# slave-16-mosfet.net
KiCad netlist of a schematic drawn in EAGLE
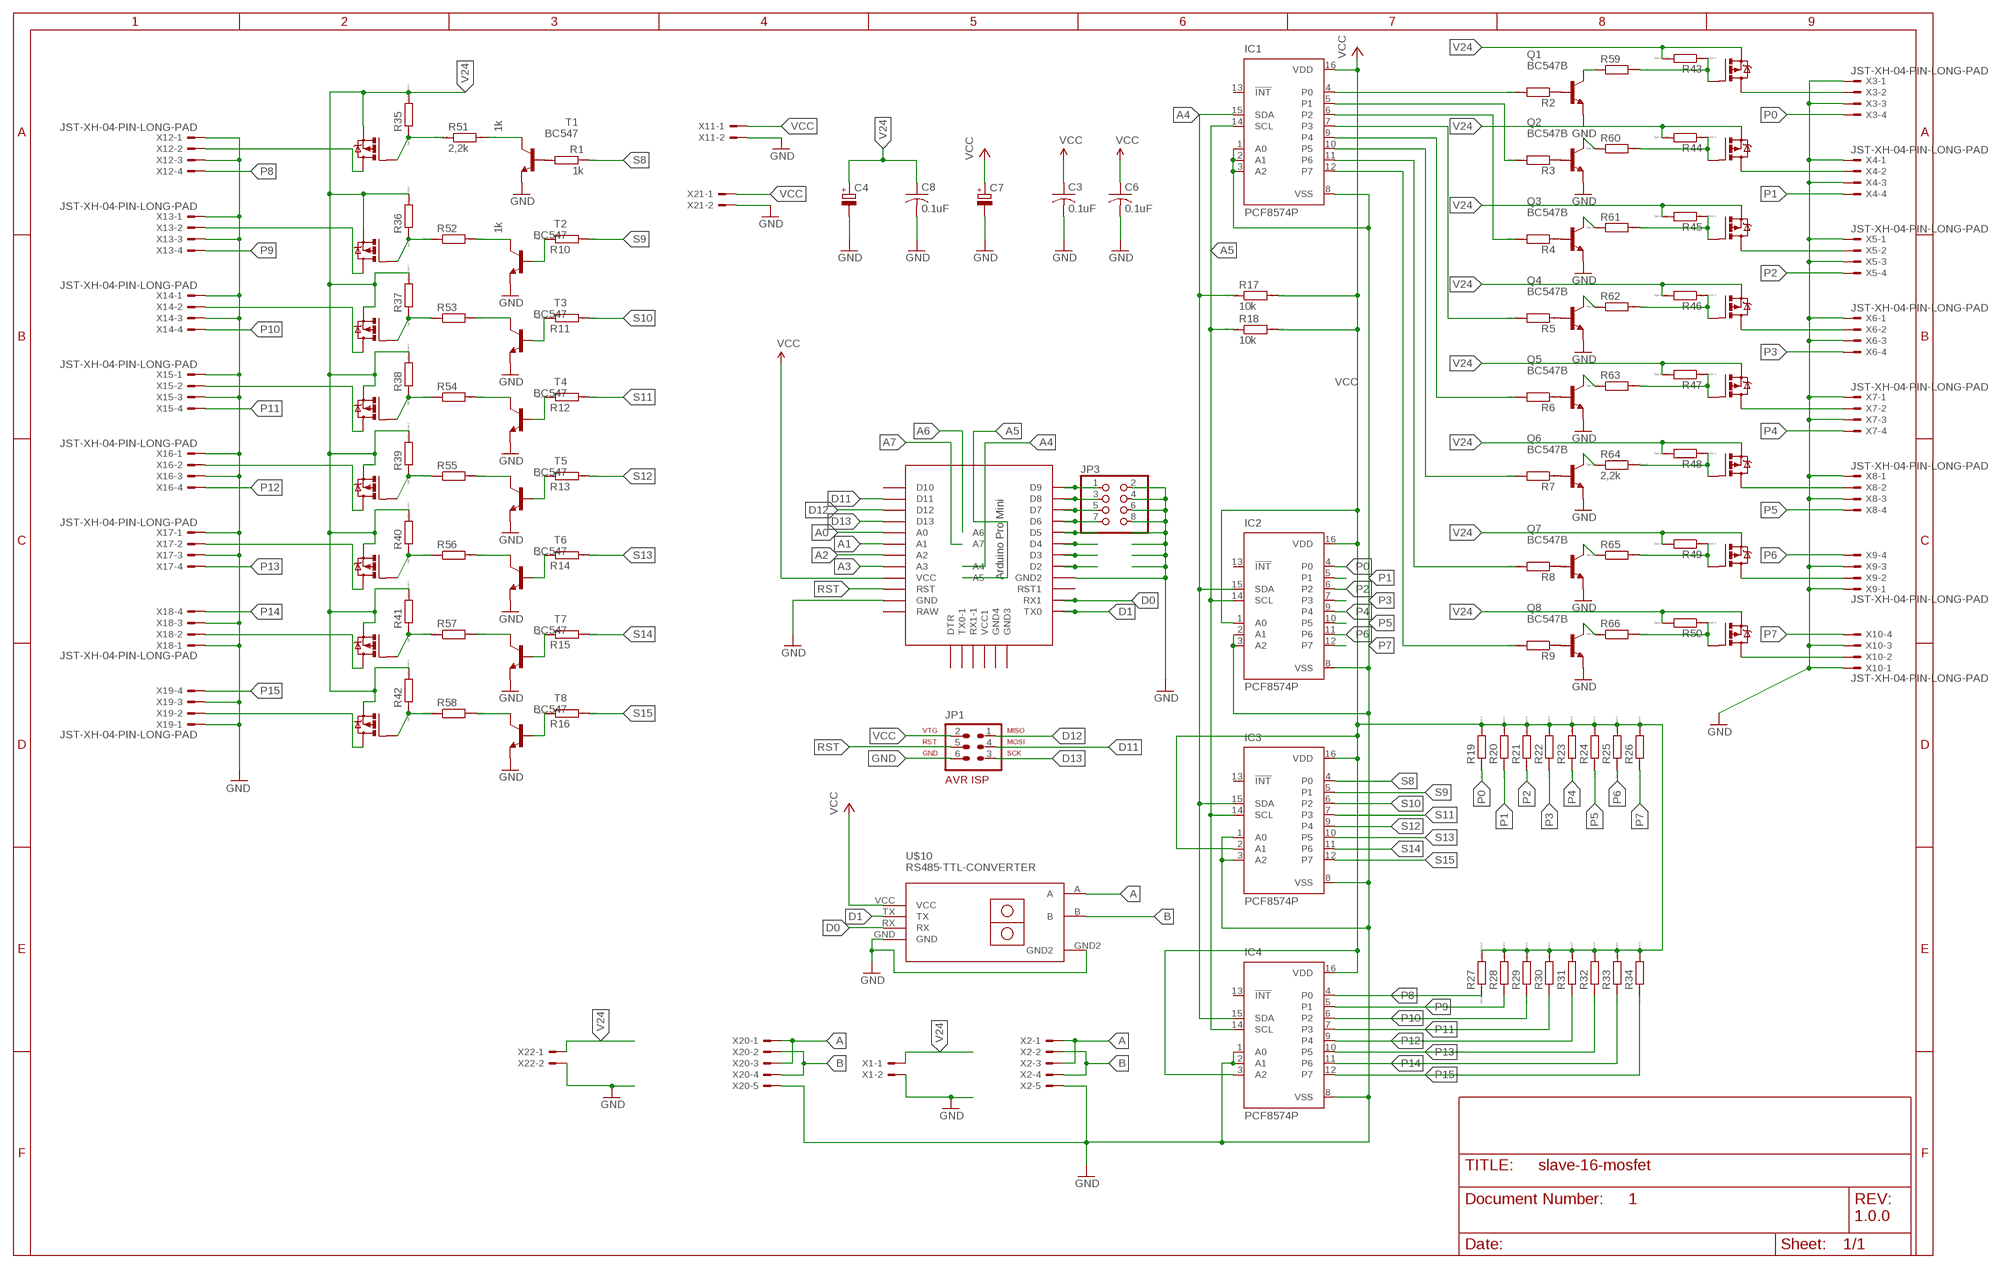
[diagram p0: schematic, sheet 1]

(export (version "E")
  (design (tool "Eeschema 10.0.6"))
  (components
    (comp (ref "C3")
      (value "0.1uF")
      (footprint "eagle-import:C0805")
      (libsource (lib "eagle-import") (part "C-USC0805"))
    )
    (comp (ref "C4")
      (value "CPOL-EUSANYO_SMD_C6")
      (footprint "eagle-import:SANYO-OSCON_SMD_C6")
      (libsource (lib "eagle-import") (part "CPOL-EUSANYO_SMD_C6"))
    )
    (comp (ref "C6")
      (value "0.1uF")
      (footprint "eagle-import:C0805")
      (libsource (lib "eagle-import") (part "C-USC0805"))
    )
    (comp (ref "C7")
      (value "CPOL-EUSANYO_SMD_C6")
      (footprint "eagle-import:SANYO-OSCON_SMD_C6")
      (libsource (lib "eagle-import") (part "CPOL-EUSANYO_SMD_C6"))
    )
    (comp (ref "C8")
      (value "0.1uF")
      (footprint "eagle-import:C0805")
      (libsource (lib "eagle-import") (part "C-USC0805"))
    )
    (comp (ref "IC1")
      (value "PCF8574P")
      (footprint "eagle-import:DIL16")
      (fields (field (name "MPN") "PCF8574PN"))
      (libsource (lib "eagle-import") (part "PCF8574P"))
    )
    (comp (ref "IC2")
      (value "PCF8574P")
      (footprint "eagle-import:DIL16")
      (fields (field (name "MPN") "PCF8574PN"))
      (libsource (lib "eagle-import") (part "PCF8574P"))
    )
    (comp (ref "IC3")
      (value "PCF8574P")
      (footprint "eagle-import:DIL16")
      (fields (field (name "MPN") "PCF8574PN"))
      (libsource (lib "eagle-import") (part "PCF8574P"))
    )
    (comp (ref "IC4")
      (value "PCF8574P")
      (footprint "eagle-import:DIL16")
      (fields (field (name "MPN") "PCF8574PN"))
      (libsource (lib "eagle-import") (part "PCF8574P"))
    )
    (comp (ref "JP1")
      (value "AVR-ISP-6")
      (footprint "eagle-import:AVR-ISP-6")
      (libsource (lib "eagle-import") (part "AVR-ISP-6"))
    )
    (comp (ref "JP3")
      (value "PINHD-2X4")
      (footprint "eagle-import:2X04")
      (libsource (lib "eagle-import") (part "PINHD-2X4"))
    )
    (comp (ref "Q1")
      (value "BC547B")
      (footprint "eagle-import:TO92")
      (libsource (lib "eagle-import") (part "BC547B"))
    )
    (comp (ref "Q2")
      (value "BC547B")
      (footprint "eagle-import:TO92")
      (libsource (lib "eagle-import") (part "BC547B"))
    )
    (comp (ref "Q3")
      (value "BC547B")
      (footprint "eagle-import:TO92")
      (libsource (lib "eagle-import") (part "BC547B"))
    )
    (comp (ref "Q4")
      (value "BC547B")
      (footprint "eagle-import:TO92")
      (libsource (lib "eagle-import") (part "BC547B"))
    )
    (comp (ref "Q5")
      (value "BC547B")
      (footprint "eagle-import:TO92")
      (libsource (lib "eagle-import") (part "BC547B"))
    )
    (comp (ref "Q6")
      (value "BC547B")
      (footprint "eagle-import:TO92")
      (libsource (lib "eagle-import") (part "BC547B"))
    )
    (comp (ref "Q7")
      (value "BC547B")
      (footprint "eagle-import:TO92")
      (libsource (lib "eagle-import") (part "BC547B"))
    )
    (comp (ref "Q8")
      (value "BC547B")
      (footprint "eagle-import:TO92")
      (libsource (lib "eagle-import") (part "BC547B"))
    )
    (comp (ref "R1")
      (value "1k")
      (footprint "eagle-import:R1206")
      (libsource (lib "eagle-import") (part "RR1206"))
    )
    (comp (ref "R2")
      (value "RR1206")
      (footprint "eagle-import:R1206")
      (libsource (lib "eagle-import") (part "RR1206"))
    )
    (comp (ref "R3")
      (value "RR1206")
      (footprint "eagle-import:R1206")
      (libsource (lib "eagle-import") (part "RR1206"))
    )
    (comp (ref "R4")
      (value "RR1206")
      (footprint "eagle-import:R1206")
      (libsource (lib "eagle-import") (part "RR1206"))
    )
    (comp (ref "R5")
      (value "RR1206")
      (footprint "eagle-import:R1206")
      (libsource (lib "eagle-import") (part "RR1206"))
    )
    (comp (ref "R6")
      (value "RR1206")
      (footprint "eagle-import:R1206")
      (libsource (lib "eagle-import") (part "RR1206"))
    )
    (comp (ref "R7")
      (value "RR1206")
      (footprint "eagle-import:R1206")
      (libsource (lib "eagle-import") (part "RR1206"))
    )
    (comp (ref "R8")
      (value "RR1206")
      (footprint "eagle-import:R1206")
      (libsource (lib "eagle-import") (part "RR1206"))
    )
    (comp (ref "R9")
      (value "RR1206")
      (footprint "eagle-import:R1206")
      (libsource (lib "eagle-import") (part "RR1206"))
    )
    (comp (ref "R10")
      (value "RR1206")
      (footprint "eagle-import:R1206")
      (libsource (lib "eagle-import") (part "RR1206"))
    )
    (comp (ref "R11")
      (value "RR1206")
      (footprint "eagle-import:R1206")
      (libsource (lib "eagle-import") (part "RR1206"))
    )
    (comp (ref "R12")
      (value "RR1206")
      (footprint "eagle-import:R1206")
      (libsource (lib "eagle-import") (part "RR1206"))
    )
    (comp (ref "R13")
      (value "RR1206")
      (footprint "eagle-import:R1206")
      (libsource (lib "eagle-import") (part "RR1206"))
    )
    (comp (ref "R14")
      (value "RR1206")
      (footprint "eagle-import:R1206")
      (libsource (lib "eagle-import") (part "RR1206"))
    )
    (comp (ref "R15")
      (value "RR1206")
      (footprint "eagle-import:R1206")
      (libsource (lib "eagle-import") (part "RR1206"))
    )
    (comp (ref "R16")
      (value "RR1206")
      (footprint "eagle-import:R1206")
      (libsource (lib "eagle-import") (part "RR1206"))
    )
    (comp (ref "R17")
      (value "10k")
      (footprint "eagle-import:R1206")
      (libsource (lib "eagle-import") (part "RR1206"))
    )
    (comp (ref "R18")
      (value "10k")
      (footprint "eagle-import:R1206")
      (libsource (lib "eagle-import") (part "RR1206"))
    )
    (comp (ref "R19")
      (value "RR1206")
      (footprint "eagle-import:R1206")
      (libsource (lib "eagle-import") (part "RR1206"))
    )
    (comp (ref "R20")
      (value "RR1206")
      (footprint "eagle-import:R1206")
      (libsource (lib "eagle-import") (part "RR1206"))
    )
    (comp (ref "R21")
      (value "RR1206")
      (footprint "eagle-import:R1206")
      (libsource (lib "eagle-import") (part "RR1206"))
    )
    (comp (ref "R22")
      (value "RR1206")
      (footprint "eagle-import:R1206")
      (libsource (lib "eagle-import") (part "RR1206"))
    )
    (comp (ref "R23")
      (value "RR1206")
      (footprint "eagle-import:R1206")
      (libsource (lib "eagle-import") (part "RR1206"))
    )
    (comp (ref "R24")
      (value "RR1206")
      (footprint "eagle-import:R1206")
      (libsource (lib "eagle-import") (part "RR1206"))
    )
    (comp (ref "R25")
      (value "RR1206")
      (footprint "eagle-import:R1206")
      (libsource (lib "eagle-import") (part "RR1206"))
    )
    (comp (ref "R26")
      (value "RR1206")
      (footprint "eagle-import:R1206")
      (libsource (lib "eagle-import") (part "RR1206"))
    )
    (comp (ref "R27")
      (value "RR1206")
      (footprint "eagle-import:R1206")
      (libsource (lib "eagle-import") (part "RR1206"))
    )
    (comp (ref "R28")
      (value "RR1206")
      (footprint "eagle-import:R1206")
      (libsource (lib "eagle-import") (part "RR1206"))
    )
    (comp (ref "R29")
      (value "RR1206")
      (footprint "eagle-import:R1206")
      (libsource (lib "eagle-import") (part "RR1206"))
    )
    (comp (ref "R30")
      (value "RR1206")
      (footprint "eagle-import:R1206")
      (libsource (lib "eagle-import") (part "RR1206"))
    )
    (comp (ref "R31")
      (value "RR1206")
      (footprint "eagle-import:R1206")
      (libsource (lib "eagle-import") (part "RR1206"))
    )
    (comp (ref "R32")
      (value "RR1206")
      (footprint "eagle-import:R1206")
      (libsource (lib "eagle-import") (part "RR1206"))
    )
    (comp (ref "R33")
      (value "RR1206")
      (footprint "eagle-import:R1206")
      (libsource (lib "eagle-import") (part "RR1206"))
    )
    (comp (ref "R34")
      (value "RR1206")
      (footprint "eagle-import:R1206")
      (libsource (lib "eagle-import") (part "RR1206"))
    )
    (comp (ref "R35")
      (value "1k")
      (footprint "eagle-import:R1206")
      (libsource (lib "eagle-import") (part "RR1206"))
    )
    (comp (ref "R36")
      (value "1k")
      (footprint "eagle-import:R1206")
      (libsource (lib "eagle-import") (part "RR1206"))
    )
    (comp (ref "R37")
      (value "RR1206")
      (footprint "eagle-import:R1206")
      (libsource (lib "eagle-import") (part "RR1206"))
    )
    (comp (ref "R38")
      (value "RR1206")
      (footprint "eagle-import:R1206")
      (libsource (lib "eagle-import") (part "RR1206"))
    )
    (comp (ref "R39")
      (value "RR1206")
      (footprint "eagle-import:R1206")
      (libsource (lib "eagle-import") (part "RR1206"))
    )
    (comp (ref "R40")
      (value "RR1206")
      (footprint "eagle-import:R1206")
      (libsource (lib "eagle-import") (part "RR1206"))
    )
    (comp (ref "R41")
      (value "RR1206")
      (footprint "eagle-import:R1206")
      (libsource (lib "eagle-import") (part "RR1206"))
    )
    (comp (ref "R42")
      (value "RR1206")
      (footprint "eagle-import:R1206")
      (libsource (lib "eagle-import") (part "RR1206"))
    )
    (comp (ref "R43")
      (value "RR1206")
      (footprint "eagle-import:R1206")
      (libsource (lib "eagle-import") (part "RR1206"))
    )
    (comp (ref "R44")
      (value "RR1206")
      (footprint "eagle-import:R1206")
      (libsource (lib "eagle-import") (part "RR1206"))
    )
    (comp (ref "R45")
      (value "RR1206")
      (footprint "eagle-import:R1206")
      (libsource (lib "eagle-import") (part "RR1206"))
    )
    (comp (ref "R46")
      (value "RR1206")
      (footprint "eagle-import:R1206")
      (libsource (lib "eagle-import") (part "RR1206"))
    )
    (comp (ref "R47")
      (value "RR1206")
      (footprint "eagle-import:R1206")
      (libsource (lib "eagle-import") (part "RR1206"))
    )
    (comp (ref "R48")
      (value "RR1206")
      (footprint "eagle-import:R1206")
      (libsource (lib "eagle-import") (part "RR1206"))
    )
    (comp (ref "R49")
      (value "RR1206")
      (footprint "eagle-import:R1206")
      (libsource (lib "eagle-import") (part "RR1206"))
    )
    (comp (ref "R50")
      (value "RR1206")
      (footprint "eagle-import:R1206")
      (libsource (lib "eagle-import") (part "RR1206"))
    )
    (comp (ref "R51")
      (value "2,2k")
      (footprint "eagle-import:R1206")
      (libsource (lib "eagle-import") (part "RR1206"))
    )
    (comp (ref "R52")
      (value "RR1206")
      (footprint "eagle-import:R1206")
      (libsource (lib "eagle-import") (part "RR1206"))
    )
    (comp (ref "R53")
      (value "RR1206")
      (footprint "eagle-import:R1206")
      (libsource (lib "eagle-import") (part "RR1206"))
    )
    (comp (ref "R54")
      (value "RR1206")
      (footprint "eagle-import:R1206")
      (libsource (lib "eagle-import") (part "RR1206"))
    )
    (comp (ref "R55")
      (value "RR1206")
      (footprint "eagle-import:R1206")
      (libsource (lib "eagle-import") (part "RR1206"))
    )
    (comp (ref "R56")
      (value "RR1206")
      (footprint "eagle-import:R1206")
      (libsource (lib "eagle-import") (part "RR1206"))
    )
    (comp (ref "R57")
      (value "RR1206")
      (footprint "eagle-import:R1206")
      (libsource (lib "eagle-import") (part "RR1206"))
    )
    (comp (ref "R58")
      (value "RR1206")
      (footprint "eagle-import:R1206")
      (libsource (lib "eagle-import") (part "RR1206"))
    )
    (comp (ref "R59")
      (value "RR1206")
      (footprint "eagle-import:R1206")
      (libsource (lib "eagle-import") (part "RR1206"))
    )
    (comp (ref "R60")
      (value "RR1206")
      (footprint "eagle-import:R1206")
      (libsource (lib "eagle-import") (part "RR1206"))
    )
    (comp (ref "R61")
      (value "RR1206")
      (footprint "eagle-import:R1206")
      (libsource (lib "eagle-import") (part "RR1206"))
    )
    (comp (ref "R62")
      (value "RR1206")
      (footprint "eagle-import:R1206")
      (libsource (lib "eagle-import") (part "RR1206"))
    )
    (comp (ref "R63")
      (value "RR1206")
      (footprint "eagle-import:R1206")
      (libsource (lib "eagle-import") (part "RR1206"))
    )
    (comp (ref "R64")
      (value "2,2k")
      (footprint "eagle-import:R1206")
      (libsource (lib "eagle-import") (part "RR1206"))
    )
    (comp (ref "R65")
      (value "RR1206")
      (footprint "eagle-import:R1206")
      (libsource (lib "eagle-import") (part "RR1206"))
    )
    (comp (ref "R66")
      (value "RR1206")
      (footprint "eagle-import:R1206")
      (libsource (lib "eagle-import") (part "RR1206"))
    )
    (comp (ref "T1")
      (value "BC547")
      (footprint "eagle-import:TO92")
      (libsource (lib "eagle-import") (part "transistor_402_BC547"))
    )
    (comp (ref "T2")
      (value "BC547")
      (footprint "eagle-import:TO92")
      (libsource (lib "eagle-import") (part "transistor_402_BC547"))
    )
    (comp (ref "T3")
      (value "BC547")
      (footprint "eagle-import:TO92")
      (libsource (lib "eagle-import") (part "transistor_402_BC547"))
    )
    (comp (ref "T4")
      (value "BC547")
      (footprint "eagle-import:TO92")
      (libsource (lib "eagle-import") (part "transistor_402_BC547"))
    )
    (comp (ref "T5")
      (value "BC547")
      (footprint "eagle-import:TO92")
      (libsource (lib "eagle-import") (part "transistor_402_BC547"))
    )
    (comp (ref "T6")
      (value "BC547")
      (footprint "eagle-import:TO92")
      (libsource (lib "eagle-import") (part "transistor_402_BC547"))
    )
    (comp (ref "T7")
      (value "BC547")
      (footprint "eagle-import:TO92")
      (libsource (lib "eagle-import") (part "transistor_402_BC547"))
    )
    (comp (ref "T8")
      (value "BC547")
      (footprint "eagle-import:TO92")
      (libsource (lib "eagle-import") (part "transistor_402_BC547"))
    )
    (comp (ref "U$1")
      (value "IRF9530")
      (footprint "eagle-import:TO220BV")
      (libsource (lib "eagle-import") (part "IRF9530"))
    )
    (comp (ref "U$2")
      (value "IRF9530")
      (footprint "eagle-import:TO220BV")
      (libsource (lib "eagle-import") (part "IRF9530"))
    )
    (comp (ref "U$3")
      (value "IRF9530")
      (footprint "eagle-import:TO220BV")
      (libsource (lib "eagle-import") (part "IRF9530"))
    )
    (comp (ref "U$4")
      (value "IRF9530")
      (footprint "eagle-import:TO220BV")
      (libsource (lib "eagle-import") (part "IRF9530"))
    )
    (comp (ref "U$5")
      (value "IRF9530")
      (footprint "eagle-import:TO220BV")
      (libsource (lib "eagle-import") (part "IRF9530"))
    )
    (comp (ref "U$6")
      (value "IRF9530")
      (footprint "eagle-import:TO220BV")
      (libsource (lib "eagle-import") (part "IRF9530"))
    )
    (comp (ref "U$7")
      (value "IRF9530")
      (footprint "eagle-import:TO220BV")
      (libsource (lib "eagle-import") (part "IRF9530"))
    )
    (comp (ref "U$8")
      (value "IRF9530")
      (footprint "eagle-import:TO220BV")
      (libsource (lib "eagle-import") (part "IRF9530"))
    )
    (comp (ref "U$10")
      (value "RS485-TTL-CONVERTER")
      (footprint "eagle-import:RS485-TTL-CONVERTER")
      (libsource (lib "eagle-import") (part "RS485-TTL-CONVERTER"))
    )
    (comp (ref "U$12")
      (value "IRF9530")
      (footprint "eagle-import:TO220BV")
      (libsource (lib "eagle-import") (part "IRF9530"))
    )
    (comp (ref "U$13")
      (value "IRF9530")
      (footprint "eagle-import:TO220BV")
      (libsource (lib "eagle-import") (part "IRF9530"))
    )
    (comp (ref "U$14")
      (value "IRF9530")
      (footprint "eagle-import:TO220BV")
      (libsource (lib "eagle-import") (part "IRF9530"))
    )
    (comp (ref "U$15")
      (value "IRF9530")
      (footprint "eagle-import:TO220BV")
      (libsource (lib "eagle-import") (part "IRF9530"))
    )
    (comp (ref "U$16")
      (value "IRF9530")
      (footprint "eagle-import:TO220BV")
      (libsource (lib "eagle-import") (part "IRF9530"))
    )
    (comp (ref "U$17")
      (value "IRF9530")
      (footprint "eagle-import:TO220BV")
      (libsource (lib "eagle-import") (part "IRF9530"))
    )
    (comp (ref "U$18")
      (value "IRF9530")
      (footprint "eagle-import:TO220BV")
      (libsource (lib "eagle-import") (part "IRF9530"))
    )
    (comp (ref "U$19")
      (value "IRF9530")
      (footprint "eagle-import:TO220BV")
      (libsource (lib "eagle-import") (part "IRF9530"))
    )
    (comp (ref "U$20")
      (value "PRO-MINI-2")
      (footprint "eagle-import:PRO-MINI-2")
      (libsource (lib "eagle-import") (part "PRO-MINI-2"))
    )
    (comp (ref "X1")
      (value "JST-XH-02-PIN-LONG-PAD")
      (footprint "eagle-import:JST-XH-02-PACKAGE-LONG-PAD")
      (libsource (lib "eagle-import") (part "JST-XH-02-PIN-LONG-PAD"))
    )
    (comp (ref "X2")
      (value "JST-XH-05-PIN-LONG-PAD")
      (footprint "eagle-import:JST-XH-05-PACKAGE-LONG-PAD")
      (libsource (lib "eagle-import") (part "JST-XH-05-PIN-LONG-PAD"))
    )
    (comp (ref "X3")
      (value "JST-XH-04-PIN-LONG-PAD")
      (footprint "eagle-import:JST-XH-04-PACKAGE-LONG-PAD")
      (libsource (lib "eagle-import") (part "JST-XH-04-PIN-LONG-PAD"))
    )
    (comp (ref "X4")
      (value "JST-XH-04-PIN-LONG-PAD")
      (footprint "eagle-import:JST-XH-04-PACKAGE-LONG-PAD")
      (libsource (lib "eagle-import") (part "JST-XH-04-PIN-LONG-PAD"))
    )
    (comp (ref "X5")
      (value "JST-XH-04-PIN-LONG-PAD")
      (footprint "eagle-import:JST-XH-04-PACKAGE-LONG-PAD")
      (libsource (lib "eagle-import") (part "JST-XH-04-PIN-LONG-PAD"))
    )
    (comp (ref "X6")
      (value "JST-XH-04-PIN-LONG-PAD")
      (footprint "eagle-import:JST-XH-04-PACKAGE-LONG-PAD")
      (libsource (lib "eagle-import") (part "JST-XH-04-PIN-LONG-PAD"))
    )
    (comp (ref "X7")
      (value "JST-XH-04-PIN-LONG-PAD")
      (footprint "eagle-import:JST-XH-04-PACKAGE-LONG-PAD")
      (libsource (lib "eagle-import") (part "JST-XH-04-PIN-LONG-PAD"))
    )
    (comp (ref "X8")
      (value "JST-XH-04-PIN-LONG-PAD")
      (footprint "eagle-import:JST-XH-04-PACKAGE-LONG-PAD")
      (libsource (lib "eagle-import") (part "JST-XH-04-PIN-LONG-PAD"))
    )
    (comp (ref "X9")
      (value "JST-XH-04-PIN-LONG-PAD")
      (footprint "eagle-import:JST-XH-04-PACKAGE-LONG-PAD")
      (libsource (lib "eagle-import") (part "JST-XH-04-PIN-LONG-PAD"))
    )
    (comp (ref "X10")
      (value "JST-XH-04-PIN-LONG-PAD")
      (footprint "eagle-import:JST-XH-04-PACKAGE-LONG-PAD")
      (libsource (lib "eagle-import") (part "JST-XH-04-PIN-LONG-PAD"))
    )
    (comp (ref "X11")
      (value "JST-XH-02-PIN-LONG-PAD")
      (footprint "eagle-import:JST-XH-02-PACKAGE-LONG-PAD")
      (libsource (lib "eagle-import") (part "JST-XH-02-PIN-LONG-PAD"))
    )
    (comp (ref "X12")
      (value "JST-XH-04-PIN-LONG-PAD")
      (footprint "eagle-import:JST-XH-04-PACKAGE-LONG-PAD")
      (libsource (lib "eagle-import") (part "JST-XH-04-PIN-LONG-PAD"))
    )
    (comp (ref "X13")
      (value "JST-XH-04-PIN-LONG-PAD")
      (footprint "eagle-import:JST-XH-04-PACKAGE-LONG-PAD")
      (libsource (lib "eagle-import") (part "JST-XH-04-PIN-LONG-PAD"))
    )
    (comp (ref "X14")
      (value "JST-XH-04-PIN-LONG-PAD")
      (footprint "eagle-import:JST-XH-04-PACKAGE-LONG-PAD")
      (libsource (lib "eagle-import") (part "JST-XH-04-PIN-LONG-PAD"))
    )
    (comp (ref "X15")
      (value "JST-XH-04-PIN-LONG-PAD")
      (footprint "eagle-import:JST-XH-04-PACKAGE-LONG-PAD")
      (libsource (lib "eagle-import") (part "JST-XH-04-PIN-LONG-PAD"))
    )
    (comp (ref "X16")
      (value "JST-XH-04-PIN-LONG-PAD")
      (footprint "eagle-import:JST-XH-04-PACKAGE-LONG-PAD")
      (libsource (lib "eagle-import") (part "JST-XH-04-PIN-LONG-PAD"))
    )
    (comp (ref "X17")
      (value "JST-XH-04-PIN-LONG-PAD")
      (footprint "eagle-import:JST-XH-04-PACKAGE-LONG-PAD")
      (libsource (lib "eagle-import") (part "JST-XH-04-PIN-LONG-PAD"))
    )
    (comp (ref "X18")
      (value "JST-XH-04-PIN-LONG-PAD")
      (footprint "eagle-import:JST-XH-04-PACKAGE-LONG-PAD")
      (libsource (lib "eagle-import") (part "JST-XH-04-PIN-LONG-PAD"))
    )
    (comp (ref "X19")
      (value "JST-XH-04-PIN-LONG-PAD")
      (footprint "eagle-import:JST-XH-04-PACKAGE-LONG-PAD")
      (libsource (lib "eagle-import") (part "JST-XH-04-PIN-LONG-PAD"))
    )
    (comp (ref "X20")
      (value "JST-XH-05-PIN-LONG-PAD")
      (footprint "eagle-import:JST-XH-05-PACKAGE-LONG-PAD")
      (libsource (lib "eagle-import") (part "JST-XH-05-PIN-LONG-PAD"))
    )
    (comp (ref "X21")
      (value "JST-XH-02-PIN-LONG-PAD")
      (footprint "eagle-import:JST-XH-02-PACKAGE-LONG-PAD")
      (libsource (lib "eagle-import") (part "JST-XH-02-PIN-LONG-PAD"))
    )
    (comp (ref "X22")
      (value "JST-XH-02-PIN-LONG-PAD")
      (footprint "eagle-import:JST-XH-02-PACKAGE-LONG-PAD")
      (libsource (lib "eagle-import") (part "JST-XH-02-PIN-LONG-PAD"))
    )
  )
  (nets
    (net (code "1") (name "A") (class "Default")
      (node (ref "U$10") (pin "A") (pinfunction "A_A") (pintype "passive"))
      (node (ref "X2") (pin "1") (pinfunction "S_1") (pintype "passive"))
      (node (ref "X2") (pin "3") (pinfunction "S_3") (pintype "passive"))
      (node (ref "X20") (pin "1") (pinfunction "S_1") (pintype "passive"))
      (node (ref "X20") (pin "3") (pinfunction "S_3") (pintype "passive"))
    )
    (net (code "2") (name "A0") (class "Default")
      (node (ref "U$20") (pin "A0") (pinfunction "A0_A0") (pintype "bidirectional"))
    )
    (net (code "3") (name "A1") (class "Default")
      (node (ref "U$20") (pin "A1") (pinfunction "A1_A1") (pintype "bidirectional"))
    )
    (net (code "4") (name "A2") (class "Default")
      (node (ref "U$20") (pin "A2") (pinfunction "A2_A2") (pintype "bidirectional"))
    )
    (net (code "5") (name "A3") (class "Default")
      (node (ref "U$20") (pin "A3") (pinfunction "A3_A3") (pintype "bidirectional"))
    )
    (net (code "6") (name "A4") (class "Default")
      (node (ref "IC1") (pin "15") (pinfunction "SDA_15") (pintype "bidirectional"))
      (node (ref "IC2") (pin "15") (pinfunction "SDA_15") (pintype "bidirectional"))
      (node (ref "IC3") (pin "15") (pinfunction "SDA_15") (pintype "bidirectional"))
      (node (ref "IC4") (pin "15") (pinfunction "SDA_15") (pintype "bidirectional"))
      (node (ref "R17") (pin "1") (pinfunction "1_1") (pintype "passive"))
      (node (ref "U$20") (pin "A4") (pinfunction "A4_A4") (pintype "bidirectional"))
    )
    (net (code "7") (name "A5") (class "Default")
      (node (ref "IC1") (pin "14") (pinfunction "SCL_14") (pintype "input"))
      (node (ref "IC2") (pin "14") (pinfunction "SCL_14") (pintype "input"))
      (node (ref "IC3") (pin "14") (pinfunction "SCL_14") (pintype "input"))
      (node (ref "IC4") (pin "14") (pinfunction "SCL_14") (pintype "input"))
      (node (ref "R18") (pin "1") (pinfunction "1_1") (pintype "passive"))
      (node (ref "U$20") (pin "A5") (pinfunction "A5_A5") (pintype "bidirectional"))
    )
    (net (code "8") (name "A6") (class "Default")
      (node (ref "U$20") (pin "A6") (pinfunction "A6_A6") (pintype "bidirectional"))
    )
    (net (code "9") (name "A7") (class "Default")
      (node (ref "U$20") (pin "A7") (pinfunction "A7_A7") (pintype "bidirectional"))
    )
    (net (code "10") (name "B") (class "Default")
      (node (ref "U$10") (pin "B") (pinfunction "B_B") (pintype "passive"))
      (node (ref "X2") (pin "2") (pinfunction "S_2") (pintype "passive"))
      (node (ref "X2") (pin "4") (pinfunction "S_4") (pintype "passive"))
      (node (ref "X20") (pin "2") (pinfunction "S_2") (pintype "passive"))
      (node (ref "X20") (pin "4") (pinfunction "S_4") (pintype "passive"))
    )
    (net (code "11") (name "D0") (class "Default")
      (node (ref "U$10") (pin "RX") (pinfunction "RX_RX") (pintype "passive"))
      (node (ref "U$20") (pin "RX1") (pinfunction "RX1_RX1") (pintype "bidirectional"))
    )
    (net (code "12") (name "D1") (class "Default")
      (node (ref "U$10") (pin "TX") (pinfunction "TX_TX") (pintype "passive"))
      (node (ref "U$20") (pin "TX0") (pinfunction "TX0_TX0") (pintype "bidirectional"))
    )
    (net (code "13") (name "D11") (class "Default")
      (node (ref "JP1") (pin "4") (pinfunction "4_4") (pintype "passive"))
      (node (ref "U$20") (pin "D11") (pinfunction "D11_D11") (pintype "bidirectional"))
    )
    (net (code "14") (name "D12") (class "Default")
      (node (ref "JP1") (pin "1") (pinfunction "1_1") (pintype "passive"))
      (node (ref "U$20") (pin "D12") (pinfunction "D12_D12") (pintype "bidirectional"))
    )
    (net (code "15") (name "D13") (class "Default")
      (node (ref "JP1") (pin "3") (pinfunction "3_3") (pintype "passive"))
      (node (ref "U$20") (pin "D13") (pinfunction "D13_D13") (pintype "bidirectional"))
    )
    (net (code "16") (name "GND") (class "Default")
      (node (ref "C3") (pin "2") (pinfunction "2_2") (pintype "passive"))
      (node (ref "C4") (pin "-") (pinfunction "-_-") (pintype "passive"))
      (node (ref "C6") (pin "2") (pinfunction "2_2") (pintype "passive"))
      (node (ref "C7") (pin "-") (pinfunction "-_-") (pintype "passive"))
      (node (ref "C8") (pin "2") (pinfunction "2_2") (pintype "passive"))
      (node (ref "IC1") (pin "1") (pinfunction "A0_1") (pintype "input"))
      (node (ref "IC1") (pin "2") (pinfunction "A1_2") (pintype "input"))
      (node (ref "IC1") (pin "3") (pinfunction "A2_3") (pintype "input"))
      (node (ref "IC1") (pin "8") (pinfunction "VSS_8") (pintype "power_in"))
      (node (ref "IC2") (pin "2") (pinfunction "A1_2") (pintype "input"))
      (node (ref "IC2") (pin "3") (pinfunction "A2_3") (pintype "input"))
      (node (ref "IC2") (pin "8") (pinfunction "VSS_8") (pintype "power_in"))
      (node (ref "IC3") (pin "1") (pinfunction "A0_1") (pintype "input"))
      (node (ref "IC3") (pin "3") (pinfunction "A2_3") (pintype "input"))
      (node (ref "IC3") (pin "8") (pinfunction "VSS_8") (pintype "power_in"))
      (node (ref "IC4") (pin "1") (pinfunction "A0_1") (pintype "input"))
      (node (ref "IC4") (pin "2") (pinfunction "A1_2") (pintype "input"))
      (node (ref "IC4") (pin "8") (pinfunction "VSS_8") (pintype "power_in"))
      (node (ref "JP1") (pin "6") (pinfunction "6_6") (pintype "passive"))
      (node (ref "JP3") (pin "2") (pinfunction "2_2") (pintype "passive"))
      (node (ref "JP3") (pin "4") (pinfunction "4_4") (pintype "passive"))
      (node (ref "JP3") (pin "6") (pinfunction "6_6") (pintype "passive"))
      (node (ref "JP3") (pin "8") (pinfunction "8_8") (pintype "passive"))
      (node (ref "Q1") (pin "1") (pinfunction "E_1") (pintype "passive"))
      (node (ref "Q2") (pin "1") (pinfunction "E_1") (pintype "passive"))
      (node (ref "Q3") (pin "1") (pinfunction "E_1") (pintype "passive"))
      (node (ref "Q4") (pin "1") (pinfunction "E_1") (pintype "passive"))
      (node (ref "Q5") (pin "1") (pinfunction "E_1") (pintype "passive"))
      (node (ref "Q6") (pin "1") (pinfunction "E_1") (pintype "passive"))
      (node (ref "Q7") (pin "1") (pinfunction "E_1") (pintype "passive"))
      (node (ref "Q8") (pin "1") (pinfunction "E_1") (pintype "passive"))
      (node (ref "T1") (pin "1") (pinfunction "E_1") (pintype "passive"))
      (node (ref "T2") (pin "1") (pinfunction "E_1") (pintype "passive"))
      (node (ref "T3") (pin "1") (pinfunction "E_1") (pintype "passive"))
      (node (ref "T4") (pin "1") (pinfunction "E_1") (pintype "passive"))
      (node (ref "T5") (pin "1") (pinfunction "E_1") (pintype "passive"))
      (node (ref "T6") (pin "1") (pinfunction "E_1") (pintype "passive"))
      (node (ref "T7") (pin "1") (pinfunction "E_1") (pintype "passive"))
      (node (ref "T8") (pin "1") (pinfunction "E_1") (pintype "passive"))
      (node (ref "U$10") (pin "GND") (pinfunction "GND_GND") (pintype "passive"))
      (node (ref "U$10") (pin "GND2") (pinfunction "GND2_GND2") (pintype "power_in"))
      (node (ref "U$20") (pin "GND") (pinfunction "GND_GND") (pintype "bidirectional"))
      (node (ref "U$20") (pin "GND1") (pinfunction "GND2_GND1") (pintype "bidirectional"))
      (node (ref "X1") (pin "2") (pinfunction "S_2") (pintype "passive"))
      (node (ref "X10") (pin "1") (pinfunction "S_1") (pintype "passive"))
      (node (ref "X10") (pin "3") (pinfunction "S_3") (pintype "passive"))
      (node (ref "X11") (pin "2") (pinfunction "S_2") (pintype "passive"))
      (node (ref "X12") (pin "1") (pinfunction "S_1") (pintype "passive"))
      (node (ref "X12") (pin "3") (pinfunction "S_3") (pintype "passive"))
      (node (ref "X13") (pin "1") (pinfunction "S_1") (pintype "passive"))
      (node (ref "X13") (pin "3") (pinfunction "S_3") (pintype "passive"))
      (node (ref "X14") (pin "1") (pinfunction "S_1") (pintype "passive"))
      (node (ref "X14") (pin "3") (pinfunction "S_3") (pintype "passive"))
      (node (ref "X15") (pin "1") (pinfunction "S_1") (pintype "passive"))
      (node (ref "X15") (pin "3") (pinfunction "S_3") (pintype "passive"))
      (node (ref "X16") (pin "1") (pinfunction "S_1") (pintype "passive"))
      (node (ref "X16") (pin "3") (pinfunction "S_3") (pintype "passive"))
      (node (ref "X17") (pin "1") (pinfunction "S_1") (pintype "passive"))
      (node (ref "X17") (pin "3") (pinfunction "S_3") (pintype "passive"))
      (node (ref "X18") (pin "1") (pinfunction "S_1") (pintype "passive"))
      (node (ref "X18") (pin "3") (pinfunction "S_3") (pintype "passive"))
      (node (ref "X19") (pin "1") (pinfunction "S_1") (pintype "passive"))
      (node (ref "X19") (pin "3") (pinfunction "S_3") (pintype "passive"))
      (node (ref "X2") (pin "5") (pinfunction "S_5") (pintype "passive"))
      (node (ref "X20") (pin "5") (pinfunction "S_5") (pintype "passive"))
      (node (ref "X21") (pin "2") (pinfunction "S_2") (pintype "passive"))
      (node (ref "X22") (pin "2") (pinfunction "S_2") (pintype "passive"))
      (node (ref "X3") (pin "1") (pinfunction "S_1") (pintype "passive"))
      (node (ref "X3") (pin "3") (pinfunction "S_3") (pintype "passive"))
      (node (ref "X4") (pin "1") (pinfunction "S_1") (pintype "passive"))
      (node (ref "X4") (pin "3") (pinfunction "S_3") (pintype "passive"))
      (node (ref "X5") (pin "1") (pinfunction "S_1") (pintype "passive"))
      (node (ref "X5") (pin "3") (pinfunction "S_3") (pintype "passive"))
      (node (ref "X6") (pin "1") (pinfunction "S_1") (pintype "passive"))
      (node (ref "X6") (pin "3") (pinfunction "S_3") (pintype "passive"))
      (node (ref "X7") (pin "1") (pinfunction "S_1") (pintype "passive"))
      (node (ref "X7") (pin "3") (pinfunction "S_3") (pintype "passive"))
      (node (ref "X8") (pin "1") (pinfunction "S_1") (pintype "passive"))
      (node (ref "X8") (pin "3") (pinfunction "S_3") (pintype "passive"))
      (node (ref "X9") (pin "1") (pinfunction "S_1") (pintype "passive"))
      (node (ref "X9") (pin "3") (pinfunction "S_3") (pintype "passive"))
    )
    (net (code "17") (name "Net-(IC1-P0)") (class "Default")
      (node (ref "IC1") (pin "4") (pinfunction "P0_4") (pintype "bidirectional"))
      (node (ref "R2") (pin "2") (pinfunction "2_2") (pintype "passive"))
    )
    (net (code "18") (name "Net-(IC1-P1)") (class "Default")
      (node (ref "IC1") (pin "5") (pinfunction "P1_5") (pintype "bidirectional"))
      (node (ref "R3") (pin "2") (pinfunction "2_2") (pintype "passive"))
    )
    (net (code "19") (name "Net-(IC1-P2)") (class "Default")
      (node (ref "IC1") (pin "6") (pinfunction "P2_6") (pintype "bidirectional"))
      (node (ref "R4") (pin "2") (pinfunction "2_2") (pintype "passive"))
    )
    (net (code "20") (name "Net-(IC1-P3)") (class "Default")
      (node (ref "IC1") (pin "7") (pinfunction "P3_7") (pintype "bidirectional"))
      (node (ref "R5") (pin "2") (pinfunction "2_2") (pintype "passive"))
    )
    (net (code "21") (name "Net-(IC1-P4)") (class "Default")
      (node (ref "IC1") (pin "9") (pinfunction "P4_9") (pintype "bidirectional"))
      (node (ref "R6") (pin "2") (pinfunction "2_2") (pintype "passive"))
    )
    (net (code "22") (name "Net-(IC1-P5)") (class "Default")
      (node (ref "IC1") (pin "10") (pinfunction "P5_10") (pintype "bidirectional"))
      (node (ref "R7") (pin "2") (pinfunction "2_2") (pintype "passive"))
    )
    (net (code "23") (name "Net-(IC1-P6)") (class "Default")
      (node (ref "IC1") (pin "11") (pinfunction "P6_11") (pintype "bidirectional"))
      (node (ref "R8") (pin "2") (pinfunction "2_2") (pintype "passive"))
    )
    (net (code "24") (name "Net-(IC1-P7)") (class "Default")
      (node (ref "IC1") (pin "12") (pinfunction "P7_12") (pintype "bidirectional"))
      (node (ref "R9") (pin "2") (pinfunction "2_2") (pintype "passive"))
    )
    (net (code "25") (name "Net-(JP3-Pad1)") (class "Default")
      (node (ref "JP3") (pin "1") (pinfunction "1_1") (pintype "passive"))
      (node (ref "U$20") (pin "D9") (pinfunction "D9_D9") (pintype "bidirectional"))
    )
    (net (code "26") (name "Net-(JP3-Pad3)") (class "Default")
      (node (ref "JP3") (pin "3") (pinfunction "3_3") (pintype "passive"))
      (node (ref "U$20") (pin "D8") (pinfunction "D8_D8") (pintype "bidirectional"))
    )
    (net (code "27") (name "Net-(JP3-Pad5)") (class "Default")
      (node (ref "JP3") (pin "5") (pinfunction "5_5") (pintype "passive"))
      (node (ref "U$20") (pin "D7") (pinfunction "D7_D7") (pintype "bidirectional"))
    )
    (net (code "28") (name "Net-(JP3-Pad7)") (class "Default")
      (node (ref "JP3") (pin "7") (pinfunction "7_7") (pintype "passive"))
      (node (ref "U$20") (pin "D6") (pinfunction "D6_D6") (pintype "bidirectional"))
    )
    (net (code "29") (name "Net-(Q1-B)") (class "Default")
      (node (ref "Q1") (pin "2") (pinfunction "B_2") (pintype "passive"))
      (node (ref "R2") (pin "1") (pinfunction "1_1") (pintype "passive"))
    )
    (net (code "30") (name "Net-(Q1-C)") (class "Default")
      (node (ref "Q1") (pin "3") (pinfunction "C_3") (pintype "passive"))
      (node (ref "R59") (pin "1") (pinfunction "1_1") (pintype "passive"))
    )
    (net (code "31") (name "Net-(Q2-B)") (class "Default")
      (node (ref "Q2") (pin "2") (pinfunction "B_2") (pintype "passive"))
      (node (ref "R3") (pin "1") (pinfunction "1_1") (pintype "passive"))
    )
    (net (code "32") (name "Net-(Q2-C)") (class "Default")
      (node (ref "Q2") (pin "3") (pinfunction "C_3") (pintype "passive"))
      (node (ref "R60") (pin "1") (pinfunction "1_1") (pintype "passive"))
    )
    (net (code "33") (name "Net-(Q3-B)") (class "Default")
      (node (ref "Q3") (pin "2") (pinfunction "B_2") (pintype "passive"))
      (node (ref "R4") (pin "1") (pinfunction "1_1") (pintype "passive"))
    )
    (net (code "34") (name "Net-(Q3-C)") (class "Default")
      (node (ref "Q3") (pin "3") (pinfunction "C_3") (pintype "passive"))
      (node (ref "R61") (pin "1") (pinfunction "1_1") (pintype "passive"))
    )
    (net (code "35") (name "Net-(Q4-B)") (class "Default")
      (node (ref "Q4") (pin "2") (pinfunction "B_2") (pintype "passive"))
      (node (ref "R5") (pin "1") (pinfunction "1_1") (pintype "passive"))
    )
    (net (code "36") (name "Net-(Q4-C)") (class "Default")
      (node (ref "Q4") (pin "3") (pinfunction "C_3") (pintype "passive"))
      (node (ref "R62") (pin "1") (pinfunction "1_1") (pintype "passive"))
    )
    (net (code "37") (name "Net-(Q5-B)") (class "Default")
      (node (ref "Q5") (pin "2") (pinfunction "B_2") (pintype "passive"))
      (node (ref "R6") (pin "1") (pinfunction "1_1") (pintype "passive"))
    )
    (net (code "38") (name "Net-(Q5-C)") (class "Default")
      (node (ref "Q5") (pin "3") (pinfunction "C_3") (pintype "passive"))
      (node (ref "R63") (pin "1") (pinfunction "1_1") (pintype "passive"))
    )
    (net (code "39") (name "Net-(Q6-B)") (class "Default")
      (node (ref "Q6") (pin "2") (pinfunction "B_2") (pintype "passive"))
      (node (ref "R7") (pin "1") (pinfunction "1_1") (pintype "passive"))
    )
    (net (code "40") (name "Net-(Q6-C)") (class "Default")
      (node (ref "Q6") (pin "3") (pinfunction "C_3") (pintype "passive"))
      (node (ref "R64") (pin "1") (pinfunction "1_1") (pintype "passive"))
    )
    (net (code "41") (name "Net-(Q7-B)") (class "Default")
      (node (ref "Q7") (pin "2") (pinfunction "B_2") (pintype "passive"))
      (node (ref "R8") (pin "1") (pinfunction "1_1") (pintype "passive"))
    )
    (net (code "42") (name "Net-(Q7-C)") (class "Default")
      (node (ref "Q7") (pin "3") (pinfunction "C_3") (pintype "passive"))
      (node (ref "R65") (pin "1") (pinfunction "1_1") (pintype "passive"))
    )
    (net (code "43") (name "Net-(Q8-B)") (class "Default")
      (node (ref "Q8") (pin "2") (pinfunction "B_2") (pintype "passive"))
      (node (ref "R9") (pin "1") (pinfunction "1_1") (pintype "passive"))
    )
    (net (code "44") (name "Net-(Q8-C)") (class "Default")
      (node (ref "Q8") (pin "3") (pinfunction "C_3") (pintype "passive"))
      (node (ref "R66") (pin "1") (pinfunction "1_1") (pintype "passive"))
    )
    (net (code "45") (name "Net-(R35-Pad1)") (class "Default")
      (node (ref "R35") (pin "1") (pinfunction "1_1") (pintype "passive"))
      (node (ref "R51") (pin "1") (pinfunction "1_1") (pintype "passive"))
      (node (ref "U$12") (pin "G") (pinfunction "G_G") (pintype "passive"))
    )
    (net (code "46") (name "Net-(R36-Pad1)") (class "Default")
      (node (ref "R36") (pin "1") (pinfunction "1_1") (pintype "passive"))
      (node (ref "R52") (pin "1") (pinfunction "1_1") (pintype "passive"))
      (node (ref "U$13") (pin "G") (pinfunction "G_G") (pintype "passive"))
    )
    (net (code "47") (name "Net-(R37-Pad1)") (class "Default")
      (node (ref "R37") (pin "1") (pinfunction "1_1") (pintype "passive"))
      (node (ref "R53") (pin "1") (pinfunction "1_1") (pintype "passive"))
      (node (ref "U$14") (pin "G") (pinfunction "G_G") (pintype "passive"))
    )
    (net (code "48") (name "Net-(R38-Pad1)") (class "Default")
      (node (ref "R38") (pin "1") (pinfunction "1_1") (pintype "passive"))
      (node (ref "R54") (pin "1") (pinfunction "1_1") (pintype "passive"))
      (node (ref "U$15") (pin "G") (pinfunction "G_G") (pintype "passive"))
    )
    (net (code "49") (name "Net-(R39-Pad1)") (class "Default")
      (node (ref "R39") (pin "1") (pinfunction "1_1") (pintype "passive"))
      (node (ref "R55") (pin "1") (pinfunction "1_1") (pintype "passive"))
      (node (ref "U$16") (pin "G") (pinfunction "G_G") (pintype "passive"))
    )
    (net (code "50") (name "Net-(R40-Pad1)") (class "Default")
      (node (ref "R40") (pin "1") (pinfunction "1_1") (pintype "passive"))
      (node (ref "R56") (pin "1") (pinfunction "1_1") (pintype "passive"))
      (node (ref "U$17") (pin "G") (pinfunction "G_G") (pintype "passive"))
    )
    (net (code "51") (name "Net-(R41-Pad1)") (class "Default")
      (node (ref "R41") (pin "1") (pinfunction "1_1") (pintype "passive"))
      (node (ref "R57") (pin "1") (pinfunction "1_1") (pintype "passive"))
      (node (ref "U$18") (pin "G") (pinfunction "G_G") (pintype "passive"))
    )
    (net (code "52") (name "Net-(R42-Pad1)") (class "Default")
      (node (ref "R42") (pin "1") (pinfunction "1_1") (pintype "passive"))
      (node (ref "R58") (pin "1") (pinfunction "1_1") (pintype "passive"))
      (node (ref "U$19") (pin "G") (pinfunction "G_G") (pintype "passive"))
    )
    (net (code "53") (name "Net-(R43-Pad1)") (class "Default")
      (node (ref "R43") (pin "1") (pinfunction "1_1") (pintype "passive"))
      (node (ref "R59") (pin "2") (pinfunction "2_2") (pintype "passive"))
      (node (ref "U$1") (pin "G") (pinfunction "G_G") (pintype "passive"))
    )
    (net (code "54") (name "Net-(R44-Pad1)") (class "Default")
      (node (ref "R44") (pin "1") (pinfunction "1_1") (pintype "passive"))
      (node (ref "R60") (pin "2") (pinfunction "2_2") (pintype "passive"))
      (node (ref "U$2") (pin "G") (pinfunction "G_G") (pintype "passive"))
    )
    (net (code "55") (name "Net-(R45-Pad1)") (class "Default")
      (node (ref "R45") (pin "1") (pinfunction "1_1") (pintype "passive"))
      (node (ref "R61") (pin "2") (pinfunction "2_2") (pintype "passive"))
      (node (ref "U$3") (pin "G") (pinfunction "G_G") (pintype "passive"))
    )
    (net (code "56") (name "Net-(R46-Pad1)") (class "Default")
      (node (ref "R46") (pin "1") (pinfunction "1_1") (pintype "passive"))
      (node (ref "R62") (pin "2") (pinfunction "2_2") (pintype "passive"))
      (node (ref "U$4") (pin "G") (pinfunction "G_G") (pintype "passive"))
    )
    (net (code "57") (name "Net-(R47-Pad1)") (class "Default")
      (node (ref "R47") (pin "1") (pinfunction "1_1") (pintype "passive"))
      (node (ref "R63") (pin "2") (pinfunction "2_2") (pintype "passive"))
      (node (ref "U$5") (pin "G") (pinfunction "G_G") (pintype "passive"))
    )
    (net (code "58") (name "Net-(R48-Pad1)") (class "Default")
      (node (ref "R48") (pin "1") (pinfunction "1_1") (pintype "passive"))
      (node (ref "R64") (pin "2") (pinfunction "2_2") (pintype "passive"))
      (node (ref "U$6") (pin "G") (pinfunction "G_G") (pintype "passive"))
    )
    (net (code "59") (name "Net-(R49-Pad1)") (class "Default")
      (node (ref "R49") (pin "1") (pinfunction "1_1") (pintype "passive"))
      (node (ref "R65") (pin "2") (pinfunction "2_2") (pintype "passive"))
      (node (ref "U$7") (pin "G") (pinfunction "G_G") (pintype "passive"))
    )
    (net (code "60") (name "Net-(R50-Pad1)") (class "Default")
      (node (ref "R50") (pin "1") (pinfunction "1_1") (pintype "passive"))
      (node (ref "R66") (pin "2") (pinfunction "2_2") (pintype "passive"))
      (node (ref "U$8") (pin "G") (pinfunction "G_G") (pintype "passive"))
    )
    (net (code "61") (name "Net-(T1-B)") (class "Default")
      (node (ref "R1") (pin "2") (pinfunction "2_2") (pintype "passive"))
      (node (ref "T1") (pin "2") (pinfunction "B_2") (pintype "passive"))
    )
    (net (code "62") (name "Net-(T1-C)") (class "Default")
      (node (ref "R51") (pin "2") (pinfunction "2_2") (pintype "passive"))
      (node (ref "T1") (pin "3") (pinfunction "C_3") (pintype "passive"))
    )
    (net (code "63") (name "Net-(T2-B)") (class "Default")
      (node (ref "R10") (pin "1") (pinfunction "1_1") (pintype "passive"))
      (node (ref "T2") (pin "2") (pinfunction "B_2") (pintype "passive"))
    )
    (net (code "64") (name "Net-(T2-C)") (class "Default")
      (node (ref "R52") (pin "2") (pinfunction "2_2") (pintype "passive"))
      (node (ref "T2") (pin "3") (pinfunction "C_3") (pintype "passive"))
    )
    (net (code "65") (name "Net-(T3-B)") (class "Default")
      (node (ref "R11") (pin "1") (pinfunction "1_1") (pintype "passive"))
      (node (ref "T3") (pin "2") (pinfunction "B_2") (pintype "passive"))
    )
    (net (code "66") (name "Net-(T3-C)") (class "Default")
      (node (ref "R53") (pin "2") (pinfunction "2_2") (pintype "passive"))
      (node (ref "T3") (pin "3") (pinfunction "C_3") (pintype "passive"))
    )
    (net (code "67") (name "Net-(T4-B)") (class "Default")
      (node (ref "R12") (pin "1") (pinfunction "1_1") (pintype "passive"))
      (node (ref "T4") (pin "2") (pinfunction "B_2") (pintype "passive"))
    )
    (net (code "68") (name "Net-(T4-C)") (class "Default")
      (node (ref "R54") (pin "2") (pinfunction "2_2") (pintype "passive"))
      (node (ref "T4") (pin "3") (pinfunction "C_3") (pintype "passive"))
    )
    (net (code "69") (name "Net-(T5-B)") (class "Default")
      (node (ref "R13") (pin "1") (pinfunction "1_1") (pintype "passive"))
      (node (ref "T5") (pin "2") (pinfunction "B_2") (pintype "passive"))
    )
    (net (code "70") (name "Net-(T5-C)") (class "Default")
      (node (ref "R55") (pin "2") (pinfunction "2_2") (pintype "passive"))
      (node (ref "T5") (pin "3") (pinfunction "C_3") (pintype "passive"))
    )
    (net (code "71") (name "Net-(T6-B)") (class "Default")
      (node (ref "R14") (pin "1") (pinfunction "1_1") (pintype "passive"))
      (node (ref "T6") (pin "2") (pinfunction "B_2") (pintype "passive"))
    )
    (net (code "72") (name "Net-(T6-C)") (class "Default")
      (node (ref "R56") (pin "2") (pinfunction "2_2") (pintype "passive"))
      (node (ref "T6") (pin "3") (pinfunction "C_3") (pintype "passive"))
    )
    (net (code "73") (name "Net-(T7-B)") (class "Default")
      (node (ref "R15") (pin "1") (pinfunction "1_1") (pintype "passive"))
      (node (ref "T7") (pin "2") (pinfunction "B_2") (pintype "passive"))
    )
    (net (code "74") (name "Net-(T7-C)") (class "Default")
      (node (ref "R57") (pin "2") (pinfunction "2_2") (pintype "passive"))
      (node (ref "T7") (pin "3") (pinfunction "C_3") (pintype "passive"))
    )
    (net (code "75") (name "Net-(T8-B)") (class "Default")
      (node (ref "R16") (pin "1") (pinfunction "1_1") (pintype "passive"))
      (node (ref "T8") (pin "2") (pinfunction "B_2") (pintype "passive"))
    )
    (net (code "76") (name "Net-(T8-C)") (class "Default")
      (node (ref "R58") (pin "2") (pinfunction "2_2") (pintype "passive"))
      (node (ref "T8") (pin "3") (pinfunction "C_3") (pintype "passive"))
    )
    (net (code "77") (name "Net-(X3B-S)") (class "Default")
      (node (ref "U$1") (pin "D") (pinfunction "D_D") (pintype "passive"))
      (node (ref "X3") (pin "2") (pinfunction "S_2") (pintype "passive"))
    )
    (net (code "78") (name "Net-(X4B-S)") (class "Default")
      (node (ref "U$2") (pin "D") (pinfunction "D_D") (pintype "passive"))
      (node (ref "X4") (pin "2") (pinfunction "S_2") (pintype "passive"))
    )
    (net (code "79") (name "Net-(X5B-S)") (class "Default")
      (node (ref "U$3") (pin "D") (pinfunction "D_D") (pintype "passive"))
      (node (ref "X5") (pin "2") (pinfunction "S_2") (pintype "passive"))
    )
    (net (code "80") (name "Net-(X6B-S)") (class "Default")
      (node (ref "U$4") (pin "D") (pinfunction "D_D") (pintype "passive"))
      (node (ref "X6") (pin "2") (pinfunction "S_2") (pintype "passive"))
    )
    (net (code "81") (name "Net-(X7B-S)") (class "Default")
      (node (ref "U$5") (pin "D") (pinfunction "D_D") (pintype "passive"))
      (node (ref "X7") (pin "2") (pinfunction "S_2") (pintype "passive"))
    )
    (net (code "82") (name "Net-(X8B-S)") (class "Default")
      (node (ref "U$6") (pin "D") (pinfunction "D_D") (pintype "passive"))
      (node (ref "X8") (pin "2") (pinfunction "S_2") (pintype "passive"))
    )
    (net (code "83") (name "Net-(X9B-S)") (class "Default")
      (node (ref "U$7") (pin "D") (pinfunction "D_D") (pintype "passive"))
      (node (ref "X9") (pin "2") (pinfunction "S_2") (pintype "passive"))
    )
    (net (code "84") (name "Net-(X10B-S)") (class "Default")
      (node (ref "U$8") (pin "D") (pinfunction "D_D") (pintype "passive"))
      (node (ref "X10") (pin "2") (pinfunction "S_2") (pintype "passive"))
    )
    (net (code "85") (name "Net-(X12B-S)") (class "Default")
      (node (ref "U$12") (pin "D") (pinfunction "D_D") (pintype "passive"))
      (node (ref "X12") (pin "2") (pinfunction "S_2") (pintype "passive"))
    )
    (net (code "86") (name "Net-(X13B-S)") (class "Default")
      (node (ref "U$13") (pin "D") (pinfunction "D_D") (pintype "passive"))
      (node (ref "X13") (pin "2") (pinfunction "S_2") (pintype "passive"))
    )
    (net (code "87") (name "Net-(X14B-S)") (class "Default")
      (node (ref "U$14") (pin "D") (pinfunction "D_D") (pintype "passive"))
      (node (ref "X14") (pin "2") (pinfunction "S_2") (pintype "passive"))
    )
    (net (code "88") (name "Net-(X15B-S)") (class "Default")
      (node (ref "U$15") (pin "D") (pinfunction "D_D") (pintype "passive"))
      (node (ref "X15") (pin "2") (pinfunction "S_2") (pintype "passive"))
    )
    (net (code "89") (name "Net-(X16B-S)") (class "Default")
      (node (ref "U$16") (pin "D") (pinfunction "D_D") (pintype "passive"))
      (node (ref "X16") (pin "2") (pinfunction "S_2") (pintype "passive"))
    )
    (net (code "90") (name "Net-(X17B-S)") (class "Default")
      (node (ref "U$17") (pin "D") (pinfunction "D_D") (pintype "passive"))
      (node (ref "X17") (pin "2") (pinfunction "S_2") (pintype "passive"))
    )
    (net (code "91") (name "Net-(X18B-S)") (class "Default")
      (node (ref "U$18") (pin "D") (pinfunction "D_D") (pintype "passive"))
      (node (ref "X18") (pin "2") (pinfunction "S_2") (pintype "passive"))
    )
    (net (code "92") (name "Net-(X19B-S)") (class "Default")
      (node (ref "U$19") (pin "D") (pinfunction "D_D") (pintype "passive"))
      (node (ref "X19") (pin "2") (pinfunction "S_2") (pintype "passive"))
    )
    (net (code "93") (name "P0") (class "Default")
      (node (ref "IC2") (pin "4") (pinfunction "P0_4") (pintype "bidirectional"))
      (node (ref "R19") (pin "1") (pinfunction "1_1") (pintype "passive"))
      (node (ref "X3") (pin "4") (pinfunction "S_4") (pintype "passive"))
    )
    (net (code "94") (name "P1") (class "Default")
      (node (ref "IC2") (pin "5") (pinfunction "P1_5") (pintype "bidirectional"))
      (node (ref "R20") (pin "1") (pinfunction "1_1") (pintype "passive"))
      (node (ref "X4") (pin "4") (pinfunction "S_4") (pintype "passive"))
    )
    (net (code "95") (name "P2") (class "Default")
      (node (ref "IC2") (pin "6") (pinfunction "P2_6") (pintype "bidirectional"))
      (node (ref "R21") (pin "1") (pinfunction "1_1") (pintype "passive"))
      (node (ref "X5") (pin "4") (pinfunction "S_4") (pintype "passive"))
    )
    (net (code "96") (name "P3") (class "Default")
      (node (ref "IC2") (pin "7") (pinfunction "P3_7") (pintype "bidirectional"))
      (node (ref "R22") (pin "1") (pinfunction "1_1") (pintype "passive"))
      (node (ref "X6") (pin "4") (pinfunction "S_4") (pintype "passive"))
    )
    (net (code "97") (name "P4") (class "Default")
      (node (ref "IC2") (pin "9") (pinfunction "P4_9") (pintype "bidirectional"))
      (node (ref "R23") (pin "1") (pinfunction "1_1") (pintype "passive"))
      (node (ref "X7") (pin "4") (pinfunction "S_4") (pintype "passive"))
    )
    (net (code "98") (name "P5") (class "Default")
      (node (ref "IC2") (pin "10") (pinfunction "P5_10") (pintype "bidirectional"))
      (node (ref "R24") (pin "1") (pinfunction "1_1") (pintype "passive"))
      (node (ref "X8") (pin "4") (pinfunction "S_4") (pintype "passive"))
    )
    (net (code "99") (name "P6") (class "Default")
      (node (ref "IC2") (pin "11") (pinfunction "P6_11") (pintype "bidirectional"))
      (node (ref "R25") (pin "1") (pinfunction "1_1") (pintype "passive"))
      (node (ref "X9") (pin "4") (pinfunction "S_4") (pintype "passive"))
    )
    (net (code "100") (name "P7") (class "Default")
      (node (ref "IC2") (pin "12") (pinfunction "P7_12") (pintype "bidirectional"))
      (node (ref "R26") (pin "1") (pinfunction "1_1") (pintype "passive"))
      (node (ref "X10") (pin "4") (pinfunction "S_4") (pintype "passive"))
    )
    (net (code "101") (name "P8") (class "Default")
      (node (ref "IC4") (pin "4") (pinfunction "P0_4") (pintype "bidirectional"))
      (node (ref "R27") (pin "1") (pinfunction "1_1") (pintype "passive"))
      (node (ref "X12") (pin "4") (pinfunction "S_4") (pintype "passive"))
    )
    (net (code "102") (name "P9") (class "Default")
      (node (ref "IC4") (pin "5") (pinfunction "P1_5") (pintype "bidirectional"))
      (node (ref "R28") (pin "1") (pinfunction "1_1") (pintype "passive"))
      (node (ref "X13") (pin "4") (pinfunction "S_4") (pintype "passive"))
    )
    (net (code "103") (name "P10") (class "Default")
      (node (ref "IC4") (pin "6") (pinfunction "P2_6") (pintype "bidirectional"))
      (node (ref "R29") (pin "1") (pinfunction "1_1") (pintype "passive"))
      (node (ref "X14") (pin "4") (pinfunction "S_4") (pintype "passive"))
    )
    (net (code "104") (name "P11") (class "Default")
      (node (ref "IC4") (pin "7") (pinfunction "P3_7") (pintype "bidirectional"))
      (node (ref "R30") (pin "1") (pinfunction "1_1") (pintype "passive"))
      (node (ref "X15") (pin "4") (pinfunction "S_4") (pintype "passive"))
    )
    (net (code "105") (name "P12") (class "Default")
      (node (ref "IC4") (pin "9") (pinfunction "P4_9") (pintype "bidirectional"))
      (node (ref "R31") (pin "1") (pinfunction "1_1") (pintype "passive"))
      (node (ref "X16") (pin "4") (pinfunction "S_4") (pintype "passive"))
    )
    (net (code "106") (name "P13") (class "Default")
      (node (ref "IC4") (pin "10") (pinfunction "P5_10") (pintype "bidirectional"))
      (node (ref "R32") (pin "1") (pinfunction "1_1") (pintype "passive"))
      (node (ref "X17") (pin "4") (pinfunction "S_4") (pintype "passive"))
    )
    (net (code "107") (name "P14") (class "Default")
      (node (ref "IC4") (pin "11") (pinfunction "P6_11") (pintype "bidirectional"))
      (node (ref "R33") (pin "1") (pinfunction "1_1") (pintype "passive"))
      (node (ref "X18") (pin "4") (pinfunction "S_4") (pintype "passive"))
    )
    (net (code "108") (name "P15") (class "Default")
      (node (ref "IC4") (pin "12") (pinfunction "P7_12") (pintype "bidirectional"))
      (node (ref "R34") (pin "1") (pinfunction "1_1") (pintype "passive"))
      (node (ref "X19") (pin "4") (pinfunction "S_4") (pintype "passive"))
    )
    (net (code "109") (name "RST") (class "Default")
      (node (ref "JP1") (pin "5") (pinfunction "5_5") (pintype "passive"))
      (node (ref "U$20") (pin "RST") (pinfunction "RST_RST") (pintype "bidirectional"))
    )
    (net (code "110") (name "S8") (class "Default")
      (node (ref "IC3") (pin "4") (pinfunction "P0_4") (pintype "bidirectional"))
      (node (ref "R1") (pin "1") (pinfunction "1_1") (pintype "passive"))
    )
    (net (code "111") (name "S9") (class "Default")
      (node (ref "IC3") (pin "5") (pinfunction "P1_5") (pintype "bidirectional"))
      (node (ref "R10") (pin "2") (pinfunction "2_2") (pintype "passive"))
    )
    (net (code "112") (name "S10") (class "Default")
      (node (ref "IC3") (pin "6") (pinfunction "P2_6") (pintype "bidirectional"))
      (node (ref "R11") (pin "2") (pinfunction "2_2") (pintype "passive"))
    )
    (net (code "113") (name "S11") (class "Default")
      (node (ref "IC3") (pin "7") (pinfunction "P3_7") (pintype "bidirectional"))
      (node (ref "R12") (pin "2") (pinfunction "2_2") (pintype "passive"))
    )
    (net (code "114") (name "S12") (class "Default")
      (node (ref "IC3") (pin "9") (pinfunction "P4_9") (pintype "bidirectional"))
      (node (ref "R13") (pin "2") (pinfunction "2_2") (pintype "passive"))
    )
    (net (code "115") (name "S13") (class "Default")
      (node (ref "IC3") (pin "10") (pinfunction "P5_10") (pintype "bidirectional"))
      (node (ref "R14") (pin "2") (pinfunction "2_2") (pintype "passive"))
    )
    (net (code "116") (name "S14") (class "Default")
      (node (ref "IC3") (pin "11") (pinfunction "P6_11") (pintype "bidirectional"))
      (node (ref "R15") (pin "2") (pinfunction "2_2") (pintype "passive"))
    )
    (net (code "117") (name "S15") (class "Default")
      (node (ref "IC3") (pin "12") (pinfunction "P7_12") (pintype "bidirectional"))
      (node (ref "R16") (pin "2") (pinfunction "2_2") (pintype "passive"))
    )
    (net (code "118") (name "V24") (class "Default")
      (node (ref "C4") (pin "+") (pinfunction "+_+") (pintype "passive"))
      (node (ref "C8") (pin "1") (pinfunction "1_1") (pintype "passive"))
      (node (ref "R35") (pin "2") (pinfunction "2_2") (pintype "passive"))
      (node (ref "R36") (pin "2") (pinfunction "2_2") (pintype "passive"))
      (node (ref "R37") (pin "2") (pinfunction "2_2") (pintype "passive"))
      (node (ref "R38") (pin "2") (pinfunction "2_2") (pintype "passive"))
      (node (ref "R39") (pin "2") (pinfunction "2_2") (pintype "passive"))
      (node (ref "R40") (pin "2") (pinfunction "2_2") (pintype "passive"))
      (node (ref "R41") (pin "2") (pinfunction "2_2") (pintype "passive"))
      (node (ref "R42") (pin "2") (pinfunction "2_2") (pintype "passive"))
      (node (ref "R43") (pin "2") (pinfunction "2_2") (pintype "passive"))
      (node (ref "R44") (pin "2") (pinfunction "2_2") (pintype "passive"))
      (node (ref "R45") (pin "2") (pinfunction "2_2") (pintype "passive"))
      (node (ref "R46") (pin "2") (pinfunction "2_2") (pintype "passive"))
      (node (ref "R47") (pin "2") (pinfunction "2_2") (pintype "passive"))
      (node (ref "R48") (pin "2") (pinfunction "2_2") (pintype "passive"))
      (node (ref "R49") (pin "2") (pinfunction "2_2") (pintype "passive"))
      (node (ref "R50") (pin "2") (pinfunction "2_2") (pintype "passive"))
      (node (ref "U$1") (pin "S") (pinfunction "S_S") (pintype "passive"))
      (node (ref "U$12") (pin "S") (pinfunction "S_S") (pintype "passive"))
      (node (ref "U$13") (pin "S") (pinfunction "S_S") (pintype "passive"))
      (node (ref "U$14") (pin "S") (pinfunction "S_S") (pintype "passive"))
      (node (ref "U$15") (pin "S") (pinfunction "S_S") (pintype "passive"))
      (node (ref "U$16") (pin "S") (pinfunction "S_S") (pintype "passive"))
      (node (ref "U$17") (pin "S") (pinfunction "S_S") (pintype "passive"))
      (node (ref "U$18") (pin "S") (pinfunction "S_S") (pintype "passive"))
      (node (ref "U$19") (pin "S") (pinfunction "S_S") (pintype "passive"))
      (node (ref "U$2") (pin "S") (pinfunction "S_S") (pintype "passive"))
      (node (ref "U$3") (pin "S") (pinfunction "S_S") (pintype "passive"))
      (node (ref "U$4") (pin "S") (pinfunction "S_S") (pintype "passive"))
      (node (ref "U$5") (pin "S") (pinfunction "S_S") (pintype "passive"))
      (node (ref "U$6") (pin "S") (pinfunction "S_S") (pintype "passive"))
      (node (ref "U$7") (pin "S") (pinfunction "S_S") (pintype "passive"))
      (node (ref "U$8") (pin "S") (pinfunction "S_S") (pintype "passive"))
      (node (ref "X1") (pin "1") (pinfunction "S_1") (pintype "passive"))
      (node (ref "X22") (pin "1") (pinfunction "S_1") (pintype "passive"))
    )
    (net (code "119") (name "VCC") (class "Default")
      (node (ref "C3") (pin "1") (pinfunction "1_1") (pintype "passive"))
      (node (ref "C6") (pin "1") (pinfunction "1_1") (pintype "passive"))
      (node (ref "C7") (pin "+") (pinfunction "+_+") (pintype "passive"))
      (node (ref "IC1") (pin "16") (pinfunction "VDD_16") (pintype "power_in"))
      (node (ref "IC2") (pin "1") (pinfunction "A0_1") (pintype "input"))
      (node (ref "IC2") (pin "16") (pinfunction "VDD_16") (pintype "power_in"))
      (node (ref "IC3") (pin "16") (pinfunction "VDD_16") (pintype "power_in"))
      (node (ref "IC3") (pin "2") (pinfunction "A1_2") (pintype "input"))
      (node (ref "IC4") (pin "16") (pinfunction "VDD_16") (pintype "power_in"))
      (node (ref "IC4") (pin "3") (pinfunction "A2_3") (pintype "input"))
      (node (ref "JP1") (pin "2") (pinfunction "2_2") (pintype "passive"))
      (node (ref "R17") (pin "2") (pinfunction "2_2") (pintype "passive"))
      (node (ref "R18") (pin "2") (pinfunction "2_2") (pintype "passive"))
      (node (ref "R19") (pin "2") (pinfunction "2_2") (pintype "passive"))
      (node (ref "R20") (pin "2") (pinfunction "2_2") (pintype "passive"))
      (node (ref "R21") (pin "2") (pinfunction "2_2") (pintype "passive"))
      (node (ref "R22") (pin "2") (pinfunction "2_2") (pintype "passive"))
      (node (ref "R23") (pin "2") (pinfunction "2_2") (pintype "passive"))
      (node (ref "R24") (pin "2") (pinfunction "2_2") (pintype "passive"))
      (node (ref "R25") (pin "2") (pinfunction "2_2") (pintype "passive"))
      (node (ref "R26") (pin "2") (pinfunction "2_2") (pintype "passive"))
      (node (ref "R27") (pin "2") (pinfunction "2_2") (pintype "passive"))
      (node (ref "R28") (pin "2") (pinfunction "2_2") (pintype "passive"))
      (node (ref "R29") (pin "2") (pinfunction "2_2") (pintype "passive"))
      (node (ref "R30") (pin "2") (pinfunction "2_2") (pintype "passive"))
      (node (ref "R31") (pin "2") (pinfunction "2_2") (pintype "passive"))
      (node (ref "R32") (pin "2") (pinfunction "2_2") (pintype "passive"))
      (node (ref "R33") (pin "2") (pinfunction "2_2") (pintype "passive"))
      (node (ref "R34") (pin "2") (pinfunction "2_2") (pintype "passive"))
      (node (ref "U$10") (pin "VCC") (pinfunction "VCC_VCC") (pintype "passive"))
      (node (ref "U$20") (pin "VCC") (pinfunction "VCC_VCC") (pintype "bidirectional"))
      (node (ref "X11") (pin "1") (pinfunction "S_1") (pintype "passive"))
      (node (ref "X21") (pin "1") (pinfunction "S_1") (pintype "passive"))
    )
    (net (code "120") (name "unconnected-(IC1-~{INT}-Pad13)") (class "Default")
      (node (ref "IC1") (pin "13") (pinfunction "~{INT}_13") (pintype "output"))
    )
    (net (code "121") (name "unconnected-(IC2-~{INT}-Pad13)") (class "Default")
      (node (ref "IC2") (pin "13") (pinfunction "~{INT}_13") (pintype "output"))
    )
    (net (code "122") (name "unconnected-(IC3-~{INT}-Pad13)") (class "Default")
      (node (ref "IC3") (pin "13") (pinfunction "~{INT}_13") (pintype "output"))
    )
    (net (code "123") (name "unconnected-(IC4-~{INT}-Pad13)") (class "Default")
      (node (ref "IC4") (pin "13") (pinfunction "~{INT}_13") (pintype "output"))
    )
    (net (code "124") (name "unconnected-(U$20-GND3-PadGND2)") (class "Default")
      (node (ref "U$20") (pin "GND2") (pinfunction "GND3_GND2") (pintype "bidirectional"))
    )
    (net (code "125") (name "unconnected-(U$20-GND4-PadGND3)") (class "Default")
      (node (ref "U$20") (pin "GND3") (pinfunction "GND4_GND3") (pintype "bidirectional"))
    )
    (net (code "126") (name "unconnected-(U$20-PadD2)") (class "Default")
      (node (ref "U$20") (pin "D2") (pinfunction "D2_D2") (pintype "bidirectional"))
    )
    (net (code "127") (name "unconnected-(U$20-PadD3)") (class "Default")
      (node (ref "U$20") (pin "D3") (pinfunction "D3_D3") (pintype "bidirectional"))
    )
    (net (code "128") (name "unconnected-(U$20-PadD4)") (class "Default")
      (node (ref "U$20") (pin "D4") (pinfunction "D4_D4") (pintype "bidirectional"))
    )
    (net (code "129") (name "unconnected-(U$20-PadD5)") (class "Default")
      (node (ref "U$20") (pin "D5") (pinfunction "D5_D5") (pintype "bidirectional"))
    )
    (net (code "130") (name "unconnected-(U$20-PadD10)") (class "Default")
      (node (ref "U$20") (pin "D10") (pinfunction "D10_D10") (pintype "bidirectional"))
    )
    (net (code "131") (name "unconnected-(U$20-PadDTR)") (class "Default")
      (node (ref "U$20") (pin "DTR") (pinfunction "DTR_DTR") (pintype "bidirectional"))
    )
    (net (code "132") (name "unconnected-(U$20-PadRAW)") (class "Default")
      (node (ref "U$20") (pin "RAW") (pinfunction "RAW_RAW") (pintype "bidirectional"))
    )
    (net (code "133") (name "unconnected-(U$20-PadRST1)") (class "Default")
      (node (ref "U$20") (pin "RST1") (pinfunction "RST1_RST1") (pintype "bidirectional"))
    )
    (net (code "134") (name "unconnected-(U$20-PadRX1-1)") (class "Default")
      (node (ref "U$20") (pin "RX1-1") (pinfunction "RX1-1_RX1-1") (pintype "bidirectional"))
    )
    (net (code "135") (name "unconnected-(U$20-PadTX0-1)") (class "Default")
      (node (ref "U$20") (pin "TX0-1") (pinfunction "TX0-1_TX0-1") (pintype "bidirectional"))
    )
    (net (code "136") (name "unconnected-(U$20-PadVCC1)") (class "Default")
      (node (ref "U$20") (pin "VCC1") (pinfunction "VCC1_VCC1") (pintype "bidirectional"))
    )
  )
)
